# C64_AV-Adaptor.net
KiCad netlist of a schematic drawn in EAGLE
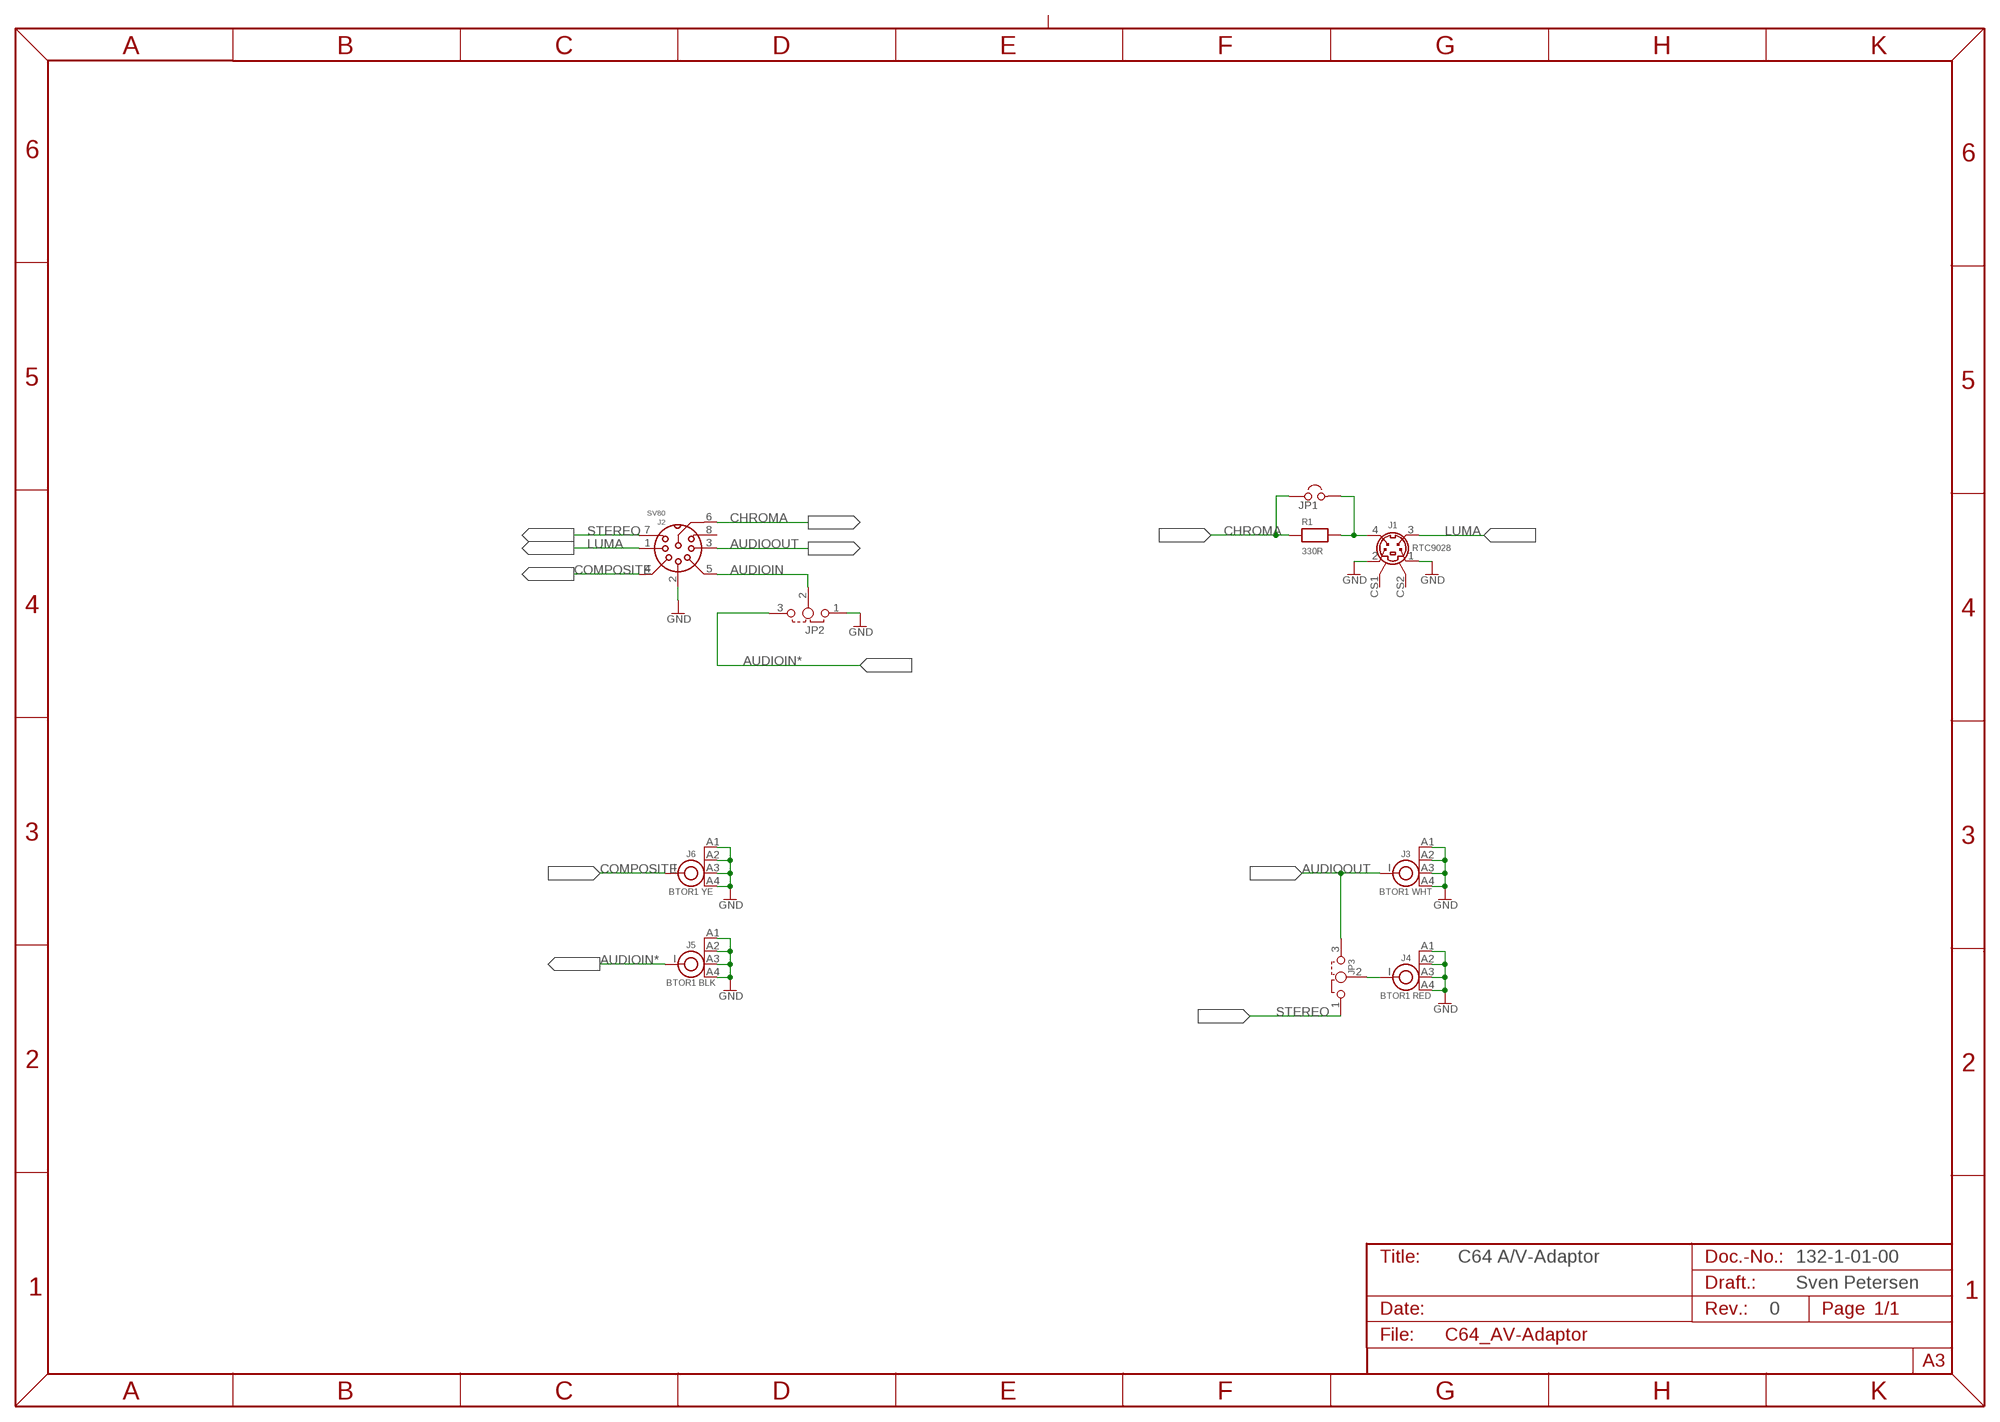
[diagram p0: schematic, sheet 1]

(export (version "E")
  (design (tool "Eeschema 10.0.6"))
  (components
    (comp (ref "J1")
      (value "RTC9028")
      (footprint "eagle-import:MINIDIN4_V")
      (libsource (lib "eagle-import") (part "RTC9028"))
    )
    (comp (ref "J2")
      (value "SV80")
      (footprint "eagle-import:SV80_INNER")
      (libsource (lib "eagle-import") (part "SV80"))
    )
    (comp (ref "J3")
      (value "BTOR1 WHT")
      (footprint "eagle-import:BTOR1")
      (libsource (lib "eagle-import") (part "BTOR1"))
    )
    (comp (ref "J4")
      (value "BTOR1 RED")
      (footprint "eagle-import:BTOR1")
      (libsource (lib "eagle-import") (part "BTOR1"))
    )
    (comp (ref "J5")
      (value "BTOR1 BLK")
      (footprint "eagle-import:BTOR1")
      (libsource (lib "eagle-import") (part "BTOR1"))
    )
    (comp (ref "J6")
      (value "BTOR1 YE")
      (footprint "eagle-import:BTOR1")
      (libsource (lib "eagle-import") (part "BTOR1"))
    )
    (comp (ref "JP1")
      (value "JUMPER")
      (footprint "eagle-import:1X02")
      (libsource (lib "eagle-import") (part "JUMPER"))
    )
    (comp (ref "JP2")
      (value "DJUMPER")
      (footprint "eagle-import:1X03")
      (libsource (lib "eagle-import") (part "DJUMPER"))
    )
    (comp (ref "JP3")
      (value "DJUMPER")
      (footprint "eagle-import:1X03")
      (libsource (lib "eagle-import") (part "DJUMPER"))
    )
    (comp (ref "R1")
      (value "330R")
      (footprint "eagle-import:R-10")
      (libsource (lib "eagle-import") (part "RES04"))
    )
  )
  (nets
    (net (code "1") (name "/AUDIOIN") (class "Default")
      (node (ref "J2") (pin "5") (pinfunction "5_5") (pintype "bidirectional"))
      (node (ref "JP2") (pin "2") (pinfunction "2_2") (pintype "bidirectional"))
    )
    (net (code "2") (name "/AUDIOIN*") (class "Default")
      (node (ref "J5") (pin "I") (pinfunction "I_I") (pintype "bidirectional"))
      (node (ref "JP2") (pin "3") (pinfunction "3_3") (pintype "bidirectional"))
    )
    (net (code "3") (name "/AUDIOOUT") (class "Default")
      (node (ref "J2") (pin "3") (pinfunction "3_3") (pintype "bidirectional"))
      (node (ref "J3") (pin "I") (pinfunction "I_I") (pintype "bidirectional"))
      (node (ref "JP3") (pin "3") (pinfunction "3_3") (pintype "bidirectional"))
    )
    (net (code "4") (name "/CHROMA") (class "Default")
      (node (ref "J2") (pin "6") (pinfunction "6_6") (pintype "bidirectional"))
      (node (ref "JP1") (pin "1") (pinfunction "1_1") (pintype "bidirectional"))
      (node (ref "R1") (pin "1") (pinfunction "1_1") (pintype "passive"))
    )
    (net (code "5") (name "/COMPOSITE") (class "Default")
      (node (ref "J2") (pin "4") (pinfunction "4_4") (pintype "bidirectional"))
      (node (ref "J6") (pin "I") (pinfunction "I_I") (pintype "bidirectional"))
    )
    (net (code "6") (name "/LUMA") (class "Default")
      (node (ref "J1") (pin "3") (pinfunction "3_3") (pintype "bidirectional"))
      (node (ref "J2") (pin "1") (pinfunction "1_1") (pintype "bidirectional"))
    )
    (net (code "7") (name "/STEREO") (class "Default")
      (node (ref "J2") (pin "7") (pinfunction "7_7") (pintype "bidirectional"))
      (node (ref "JP3") (pin "1") (pinfunction "1_1") (pintype "bidirectional"))
    )
    (net (code "8") (name "GND") (class "Default")
      (node (ref "J1") (pin "1") (pinfunction "1_1") (pintype "bidirectional"))
      (node (ref "J1") (pin "2") (pinfunction "2_2") (pintype "bidirectional"))
      (node (ref "J2") (pin "2") (pinfunction "2_2") (pintype "bidirectional"))
      (node (ref "J3") (pin "A1") (pinfunction "A1_A1") (pintype "bidirectional"))
      (node (ref "J3") (pin "A2") (pinfunction "A2_A2") (pintype "bidirectional"))
      (node (ref "J3") (pin "A3") (pinfunction "A3_A3") (pintype "bidirectional"))
      (node (ref "J3") (pin "A4") (pinfunction "A4_A4") (pintype "bidirectional"))
      (node (ref "J4") (pin "A1") (pinfunction "A1_A1") (pintype "bidirectional"))
      (node (ref "J4") (pin "A2") (pinfunction "A2_A2") (pintype "bidirectional"))
      (node (ref "J4") (pin "A3") (pinfunction "A3_A3") (pintype "bidirectional"))
      (node (ref "J4") (pin "A4") (pinfunction "A4_A4") (pintype "bidirectional"))
      (node (ref "J5") (pin "A1") (pinfunction "A1_A1") (pintype "bidirectional"))
      (node (ref "J5") (pin "A2") (pinfunction "A2_A2") (pintype "bidirectional"))
      (node (ref "J5") (pin "A3") (pinfunction "A3_A3") (pintype "bidirectional"))
      (node (ref "J5") (pin "A4") (pinfunction "A4_A4") (pintype "bidirectional"))
      (node (ref "J6") (pin "A1") (pinfunction "A1_A1") (pintype "bidirectional"))
      (node (ref "J6") (pin "A2") (pinfunction "A2_A2") (pintype "bidirectional"))
      (node (ref "J6") (pin "A3") (pinfunction "A3_A3") (pintype "bidirectional"))
      (node (ref "J6") (pin "A4") (pinfunction "A4_A4") (pintype "bidirectional"))
      (node (ref "JP2") (pin "1") (pinfunction "1_1") (pintype "bidirectional"))
    )
    (net (code "9") (name "Net-(J1-Pad4)") (class "Default")
      (node (ref "J1") (pin "4") (pinfunction "4_4") (pintype "bidirectional"))
      (node (ref "JP1") (pin "2") (pinfunction "2_2") (pintype "bidirectional"))
      (node (ref "R1") (pin "2") (pinfunction "2_2") (pintype "passive"))
    )
    (net (code "10") (name "Net-(J4-PadI)") (class "Default")
      (node (ref "J4") (pin "I") (pinfunction "I_I") (pintype "bidirectional"))
      (node (ref "JP3") (pin "2") (pinfunction "2_2") (pintype "bidirectional"))
    )
    (net (code "11") (name "unconnected-(J1-PadCS1)") (class "Default")
      (node (ref "J1") (pin "CS1") (pinfunction "CS1_CS1") (pintype "bidirectional"))
    )
    (net (code "12") (name "unconnected-(J1-PadCS2)") (class "Default")
      (node (ref "J1") (pin "CS2") (pinfunction "CS2_CS2") (pintype "bidirectional"))
    )
    (net (code "13") (name "unconnected-(J2-Pad8)") (class "Default")
      (node (ref "J2") (pin "8") (pinfunction "8_8") (pintype "bidirectional"))
    )
  )
)
